# Symposion_K3_Arduino-Peripherie-IF_v2_2.net
KiCad netlist of a schematic drawn in EAGLE
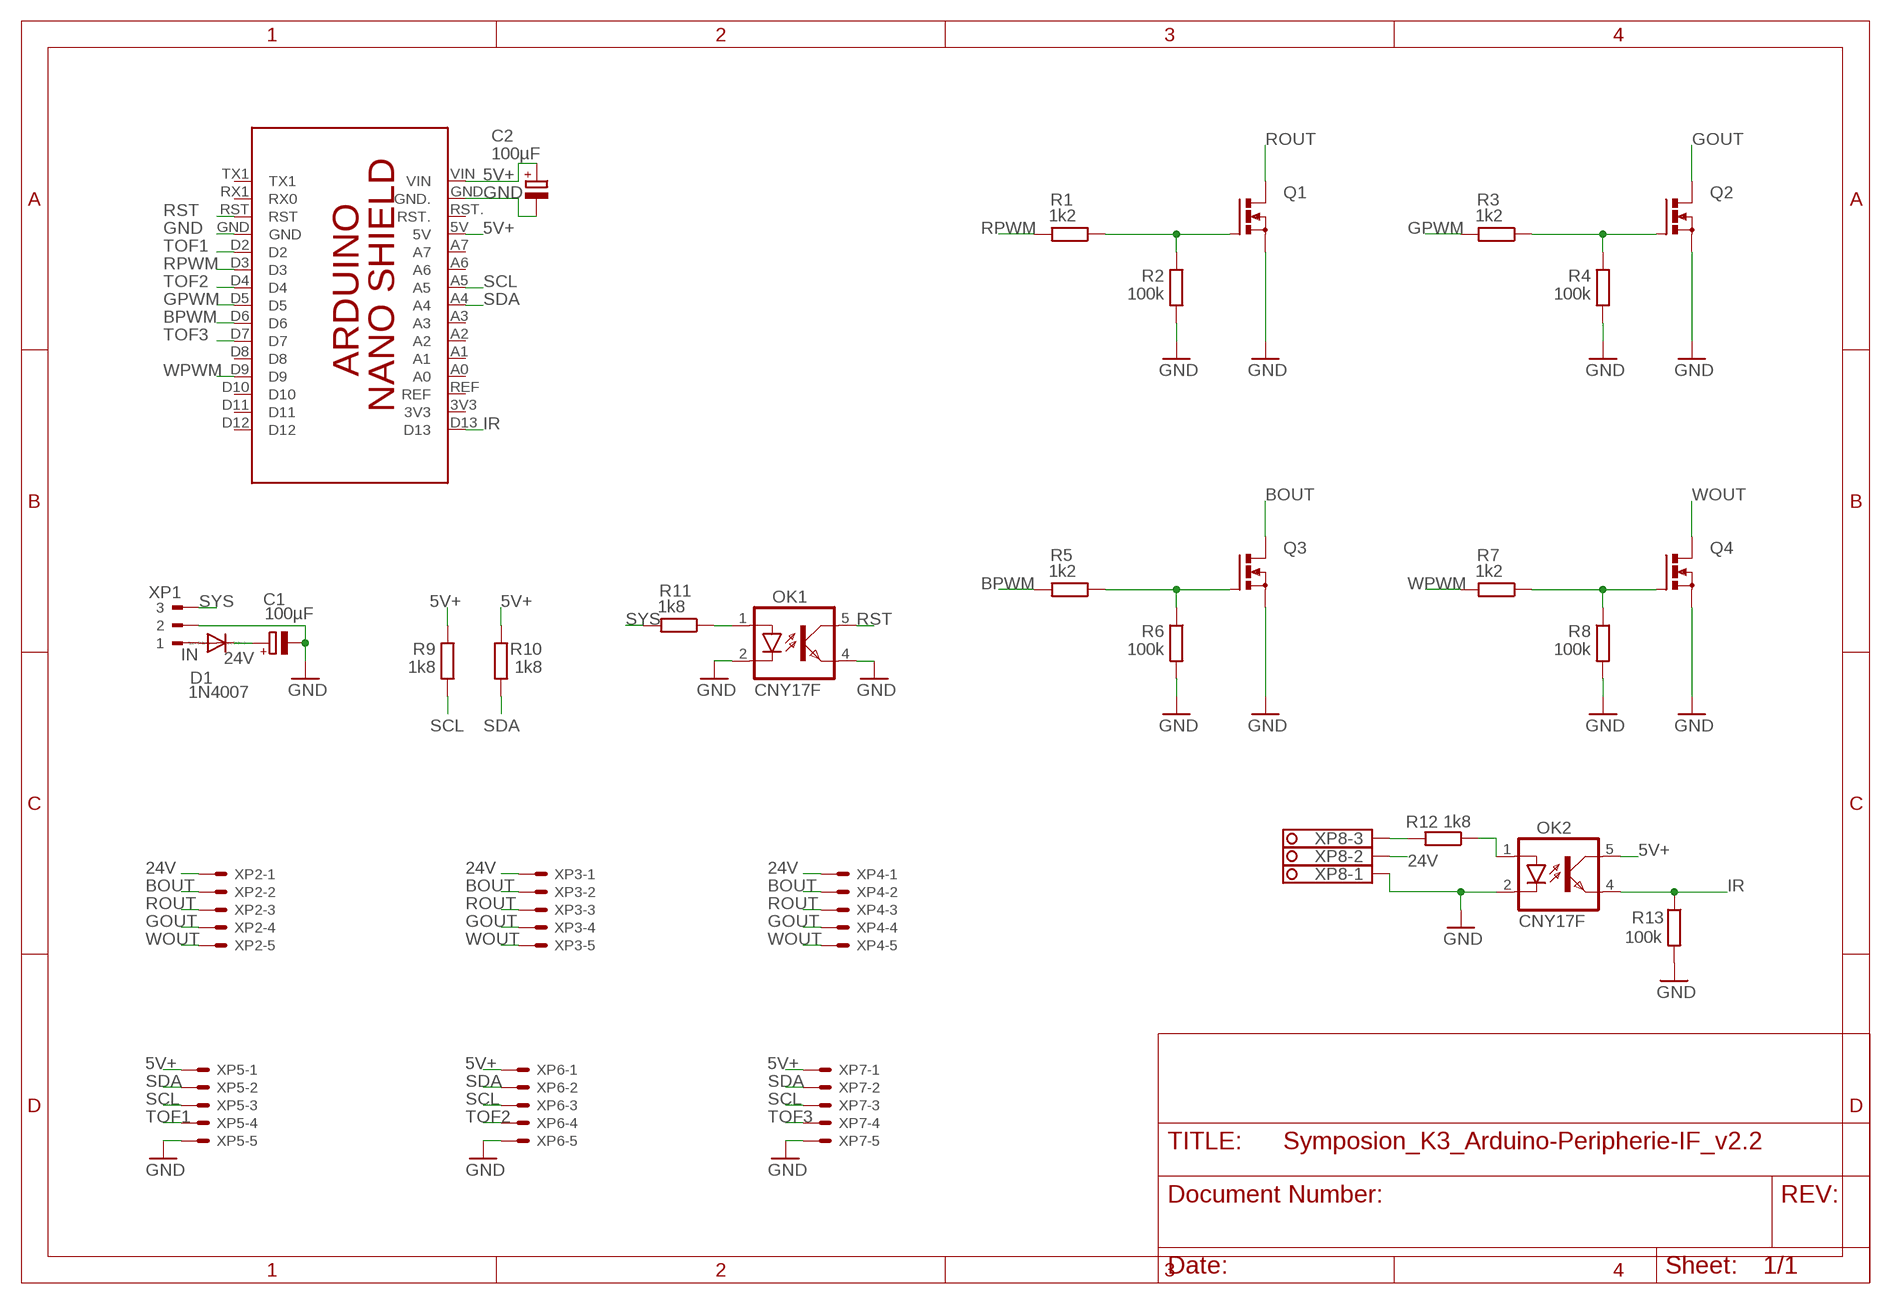
[diagram p0: schematic, sheet 1]

(export (version "E")
  (design (tool "Eeschema 10.0.6"))
  (components
    (comp (ref "C1")
      (value "100µF")
      (footprint "eagle-import:RCL_E5-6")
      (libsource (lib "eagle-import") (part "RCL_CPOL-EUE5-6"))
    )
    (comp (ref "C2")
      (value "100µF")
      (footprint "eagle-import:RCL_E5-6")
      (libsource (lib "eagle-import") (part "RCL_CPOL-EUE5-6"))
    )
    (comp (ref "D1")
      (value "1N4007")
      (footprint "eagle-import:DIODE_F126-10")
      (libsource (lib "eagle-import") (part "DIODE_DIODE-F126-10"))
    )
    (comp (ref "OK1")
      (value "CNY17F")
      (footprint "eagle-import:DIL06")
      (fields (field (name "MF") "VISHAY/TELEFUNKEN") (field (name "MPN") "CNY17F-3"))
      (libsource (lib "eagle-import") (part "CNY17F"))
    )
    (comp (ref "OK2")
      (value "CNY17F")
      (footprint "eagle-import:DIL06")
      (fields (field (name "MF") "VISHAY/TELEFUNKEN") (field (name "MPN") "CNY17F-3"))
      (libsource (lib "eagle-import") (part "CNY17F"))
    )
    (comp (ref "PCB1")
      (value "0_WSH_FAVORITES_ARDUINO_NANO")
      (footprint "eagle-import:0_WSH_FAVORITES_ARDUINO_NANO")
      (libsource (lib "eagle-import") (part "0_WSH_FAVORITES_ARDUINO_NANO"))
    )
    (comp (ref "Q1")
      (value "0_WSH_FAVORITES_BUZ11BV")
      (footprint "eagle-import:0_WSH_FAVORITES_TO220BV")
      (libsource (lib "eagle-import") (part "0_WSH_FAVORITES_BUZ11BV"))
    )
    (comp (ref "Q2")
      (value "0_WSH_FAVORITES_BUZ11BV")
      (footprint "eagle-import:0_WSH_FAVORITES_TO220BV")
      (libsource (lib "eagle-import") (part "0_WSH_FAVORITES_BUZ11BV"))
    )
    (comp (ref "Q3")
      (value "0_WSH_FAVORITES_BUZ11BV")
      (footprint "eagle-import:0_WSH_FAVORITES_TO220BV")
      (libsource (lib "eagle-import") (part "0_WSH_FAVORITES_BUZ11BV"))
    )
    (comp (ref "Q4")
      (value "0_WSH_FAVORITES_BUZ11BV")
      (footprint "eagle-import:0_WSH_FAVORITES_TO220BV")
      (libsource (lib "eagle-import") (part "0_WSH_FAVORITES_BUZ11BV"))
    )
    (comp (ref "R1")
      (value "1k2")
      (footprint "eagle-import:R1206")
      (libsource (lib "eagle-import") (part "R-EU_R1206"))
    )
    (comp (ref "R2")
      (value "100k")
      (footprint "eagle-import:R1206")
      (libsource (lib "eagle-import") (part "R-EU_R1206"))
    )
    (comp (ref "R3")
      (value "1k2")
      (footprint "eagle-import:R1206")
      (libsource (lib "eagle-import") (part "R-EU_R1206"))
    )
    (comp (ref "R4")
      (value "100k")
      (footprint "eagle-import:R1206")
      (libsource (lib "eagle-import") (part "R-EU_R1206"))
    )
    (comp (ref "R5")
      (value "1k2")
      (footprint "eagle-import:R1206")
      (libsource (lib "eagle-import") (part "R-EU_R1206"))
    )
    (comp (ref "R6")
      (value "100k")
      (footprint "eagle-import:R1206")
      (libsource (lib "eagle-import") (part "R-EU_R1206"))
    )
    (comp (ref "R7")
      (value "1k2")
      (footprint "eagle-import:R1206")
      (libsource (lib "eagle-import") (part "R-EU_R1206"))
    )
    (comp (ref "R8")
      (value "100k")
      (footprint "eagle-import:R1206")
      (libsource (lib "eagle-import") (part "R-EU_R1206"))
    )
    (comp (ref "R9")
      (value "1k8")
      (footprint "eagle-import:R1206")
      (libsource (lib "eagle-import") (part "R-EU_R1206"))
    )
    (comp (ref "R10")
      (value "1k8")
      (footprint "eagle-import:R1206")
      (libsource (lib "eagle-import") (part "R-EU_R1206"))
    )
    (comp (ref "R11")
      (value "1k8")
      (footprint "eagle-import:R1206")
      (libsource (lib "eagle-import") (part "R-EU_R1206"))
    )
    (comp (ref "R12")
      (value "1k8")
      (footprint "eagle-import:R1206")
      (libsource (lib "eagle-import") (part "R-EU_R1206"))
    )
    (comp (ref "R13")
      (value "100k")
      (footprint "eagle-import:R1206")
      (libsource (lib "eagle-import") (part "R-EU_R1206"))
    )
    (comp (ref "XP1")
      (value "180-3")
      (footprint "eagle-import:180-3")
      (libsource (lib "eagle-import") (part "180-3"))
    )
    (comp (ref "XP2")
      (value "22-27-2051-05")
      (footprint "eagle-import:6410-05")
      (fields (field (name "MF") "MOLEX"))
      (libsource (lib "eagle-import") (part "22-?-0527-2051"))
    )
    (comp (ref "XP3")
      (value "22-27-2051-05")
      (footprint "eagle-import:6410-05")
      (fields (field (name "MF") "MOLEX"))
      (libsource (lib "eagle-import") (part "22-?-0527-2051"))
    )
    (comp (ref "XP4")
      (value "22-27-2051-05")
      (footprint "eagle-import:6410-05")
      (fields (field (name "MF") "MOLEX"))
      (libsource (lib "eagle-import") (part "22-?-0527-2051"))
    )
    (comp (ref "XP5")
      (value "22-27-2051-05")
      (footprint "eagle-import:6410-05")
      (fields (field (name "MF") "MOLEX"))
      (libsource (lib "eagle-import") (part "22-?-0527-2051"))
    )
    (comp (ref "XP6")
      (value "22-27-2051-05")
      (footprint "eagle-import:6410-05")
      (fields (field (name "MF") "MOLEX"))
      (libsource (lib "eagle-import") (part "22-?-0527-2051"))
    )
    (comp (ref "XP7")
      (value "22-27-2051-05")
      (footprint "eagle-import:6410-05")
      (fields (field (name "MF") "MOLEX"))
      (libsource (lib "eagle-import") (part "22-?-0527-2051"))
    )
    (comp (ref "XP8")
      (value "1751251")
      (footprint "eagle-import:1751251")
      (libsource (lib "eagle-import") (part "1751251"))
    )
  )
  (nets
    (net (code "1") (name "/5V+") (class "Default")
      (node (ref "C2") (pin "+") (pinfunction "+_+") (pintype "passive"))
      (node (ref "OK2") (pin "5") (pinfunction "COL_5") (pintype "passive"))
      (node (ref "PCB1") (pin "5V") (pinfunction "5V_5V") (pintype "bidirectional"))
      (node (ref "PCB1") (pin "VIN") (pinfunction "VIN_VIN") (pintype "bidirectional"))
      (node (ref "R10") (pin "1") (pinfunction "1_1") (pintype "passive"))
      (node (ref "R9") (pin "1") (pinfunction "1_1") (pintype "passive"))
      (node (ref "XP5") (pin "1") (pinfunction "S_1") (pintype "passive"))
      (node (ref "XP6") (pin "1") (pinfunction "S_1") (pintype "passive"))
      (node (ref "XP7") (pin "1") (pinfunction "S_1") (pintype "passive"))
    )
    (net (code "2") (name "/24V") (class "Default")
      (node (ref "C1") (pin "+") (pinfunction "+_+") (pintype "passive"))
      (node (ref "D1") (pin "C") (pinfunction "C_C") (pintype "passive"))
      (node (ref "XP2") (pin "1") (pinfunction "S_1") (pintype "passive"))
      (node (ref "XP3") (pin "1") (pinfunction "S_1") (pintype "passive"))
      (node (ref "XP4") (pin "1") (pinfunction "S_1") (pintype "passive"))
      (node (ref "XP8") (pin "2") (pinfunction "K_2") (pintype "passive"))
    )
    (net (code "3") (name "/BOUT") (class "Default")
      (node (ref "Q3") (pin "D") (pinfunction "D_D") (pintype "passive"))
      (node (ref "XP2") (pin "2") (pinfunction "S_2") (pintype "passive"))
      (node (ref "XP3") (pin "2") (pinfunction "S_2") (pintype "passive"))
      (node (ref "XP4") (pin "2") (pinfunction "S_2") (pintype "passive"))
    )
    (net (code "4") (name "/BPWM") (class "Default")
      (node (ref "PCB1") (pin "D6") (pinfunction "D6_D6") (pintype "bidirectional"))
      (node (ref "R5") (pin "2") (pinfunction "2_2") (pintype "passive"))
    )
    (net (code "5") (name "/GOUT") (class "Default")
      (node (ref "Q2") (pin "D") (pinfunction "D_D") (pintype "passive"))
      (node (ref "XP2") (pin "4") (pinfunction "S_4") (pintype "passive"))
      (node (ref "XP3") (pin "4") (pinfunction "S_4") (pintype "passive"))
      (node (ref "XP4") (pin "4") (pinfunction "S_4") (pintype "passive"))
    )
    (net (code "6") (name "/GPWM") (class "Default")
      (node (ref "PCB1") (pin "D5") (pinfunction "D5_D5") (pintype "bidirectional"))
      (node (ref "R3") (pin "2") (pinfunction "2_2") (pintype "passive"))
    )
    (net (code "8") (name "/IR") (class "Default")
      (node (ref "OK2") (pin "4") (pinfunction "EMIT_4") (pintype "passive"))
      (node (ref "PCB1") (pin "D13") (pinfunction "D13_D13") (pintype "bidirectional"))
      (node (ref "R13") (pin "1") (pinfunction "1_1") (pintype "passive"))
    )
    (net (code "9") (name "/ROUT") (class "Default")
      (node (ref "Q1") (pin "D") (pinfunction "D_D") (pintype "passive"))
      (node (ref "XP2") (pin "3") (pinfunction "S_3") (pintype "passive"))
      (node (ref "XP3") (pin "3") (pinfunction "S_3") (pintype "passive"))
      (node (ref "XP4") (pin "3") (pinfunction "S_3") (pintype "passive"))
    )
    (net (code "10") (name "/RPWM") (class "Default")
      (node (ref "PCB1") (pin "D3") (pinfunction "D3_D3") (pintype "bidirectional"))
      (node (ref "R1") (pin "2") (pinfunction "2_2") (pintype "passive"))
    )
    (net (code "11") (name "/RST") (class "Default")
      (node (ref "OK1") (pin "5") (pinfunction "COL_5") (pintype "passive"))
      (node (ref "PCB1") (pin "RST") (pinfunction "RST_RST") (pintype "bidirectional"))
    )
    (net (code "12") (name "/SCL") (class "Default")
      (node (ref "PCB1") (pin "A5") (pinfunction "A5_A5") (pintype "bidirectional"))
      (node (ref "R9") (pin "2") (pinfunction "2_2") (pintype "passive"))
      (node (ref "XP5") (pin "3") (pinfunction "S_3") (pintype "passive"))
      (node (ref "XP6") (pin "3") (pinfunction "S_3") (pintype "passive"))
      (node (ref "XP7") (pin "3") (pinfunction "S_3") (pintype "passive"))
    )
    (net (code "13") (name "/SDA") (class "Default")
      (node (ref "PCB1") (pin "A4") (pinfunction "A4_A4") (pintype "bidirectional"))
      (node (ref "R10") (pin "2") (pinfunction "2_2") (pintype "passive"))
      (node (ref "XP5") (pin "2") (pinfunction "S_2") (pintype "passive"))
      (node (ref "XP6") (pin "2") (pinfunction "S_2") (pintype "passive"))
      (node (ref "XP7") (pin "2") (pinfunction "S_2") (pintype "passive"))
    )
    (net (code "14") (name "/SYS") (class "Default")
      (node (ref "R11") (pin "2") (pinfunction "2_2") (pintype "passive"))
      (node (ref "XP1") (pin "3") (pinfunction "3_3") (pintype "passive"))
    )
    (net (code "15") (name "/TOF1") (class "Default")
      (node (ref "PCB1") (pin "D2") (pinfunction "D2_D2") (pintype "bidirectional"))
      (node (ref "XP5") (pin "4") (pinfunction "S_4") (pintype "passive"))
    )
    (net (code "16") (name "/TOF2") (class "Default")
      (node (ref "PCB1") (pin "D4") (pinfunction "D4_D4") (pintype "bidirectional"))
      (node (ref "XP6") (pin "4") (pinfunction "S_4") (pintype "passive"))
    )
    (net (code "17") (name "/TOF3") (class "Default")
      (node (ref "PCB1") (pin "D7") (pinfunction "D7_D7") (pintype "bidirectional"))
      (node (ref "XP7") (pin "4") (pinfunction "S_4") (pintype "passive"))
    )
    (net (code "18") (name "/WOUT") (class "Default")
      (node (ref "Q4") (pin "D") (pinfunction "D_D") (pintype "passive"))
      (node (ref "XP2") (pin "5") (pinfunction "S_5") (pintype "passive"))
      (node (ref "XP3") (pin "5") (pinfunction "S_5") (pintype "passive"))
      (node (ref "XP4") (pin "5") (pinfunction "S_5") (pintype "passive"))
    )
    (net (code "19") (name "/WPWM") (class "Default")
      (node (ref "PCB1") (pin "D9") (pinfunction "D9_D9") (pintype "bidirectional"))
      (node (ref "R7") (pin "2") (pinfunction "2_2") (pintype "passive"))
    )
    (net (code "20") (name "GND") (class "Default")
      (node (ref "C1") (pin "-") (pinfunction "-_-") (pintype "passive"))
      (node (ref "C2") (pin "-") (pinfunction "-_-") (pintype "passive"))
      (node (ref "OK1") (pin "2") (pinfunction "C_2") (pintype "passive"))
      (node (ref "OK1") (pin "4") (pinfunction "EMIT_4") (pintype "passive"))
      (node (ref "OK2") (pin "2") (pinfunction "C_2") (pintype "passive"))
      (node (ref "PCB1") (pin "GND") (pinfunction "GND_GND") (pintype "bidirectional"))
      (node (ref "PCB1") (pin "GND.") (pinfunction "GND._GND.") (pintype "bidirectional"))
      (node (ref "Q1") (pin "S") (pinfunction "S_S") (pintype "passive"))
      (node (ref "Q2") (pin "S") (pinfunction "S_S") (pintype "passive"))
      (node (ref "Q3") (pin "S") (pinfunction "S_S") (pintype "passive"))
      (node (ref "Q4") (pin "S") (pinfunction "S_S") (pintype "passive"))
      (node (ref "R13") (pin "2") (pinfunction "2_2") (pintype "passive"))
      (node (ref "R2") (pin "2") (pinfunction "2_2") (pintype "passive"))
      (node (ref "R4") (pin "2") (pinfunction "2_2") (pintype "passive"))
      (node (ref "R6") (pin "2") (pinfunction "2_2") (pintype "passive"))
      (node (ref "R8") (pin "2") (pinfunction "2_2") (pintype "passive"))
      (node (ref "XP1") (pin "2") (pinfunction "2_2") (pintype "passive"))
      (node (ref "XP5") (pin "5") (pinfunction "S_5") (pintype "passive"))
      (node (ref "XP6") (pin "5") (pinfunction "S_5") (pintype "passive"))
      (node (ref "XP7") (pin "5") (pinfunction "S_5") (pintype "passive"))
      (node (ref "XP8") (pin "1") (pinfunction "K_1") (pintype "passive"))
    )
    (net (code "21") (name "Net-(D1-PadA)") (class "Default")
      (node (ref "D1") (pin "A") (pinfunction "A_A") (pintype "passive"))
      (node (ref "XP1") (pin "1") (pinfunction "1_1") (pintype "passive"))
    )
    (net (code "22") (name "Net-(OK1-A)") (class "Default")
      (node (ref "OK1") (pin "1") (pinfunction "A_1") (pintype "passive"))
      (node (ref "R11") (pin "1") (pinfunction "1_1") (pintype "passive"))
    )
    (net (code "23") (name "Net-(OK2-A)") (class "Default")
      (node (ref "OK2") (pin "1") (pinfunction "A_1") (pintype "passive"))
      (node (ref "R12") (pin "1") (pinfunction "1_1") (pintype "passive"))
    )
    (net (code "24") (name "Net-(Q1-PadG)") (class "Default")
      (node (ref "Q1") (pin "G") (pinfunction "G_G") (pintype "passive"))
      (node (ref "R1") (pin "1") (pinfunction "1_1") (pintype "passive"))
      (node (ref "R2") (pin "1") (pinfunction "1_1") (pintype "passive"))
    )
    (net (code "25") (name "Net-(Q2-PadG)") (class "Default")
      (node (ref "Q2") (pin "G") (pinfunction "G_G") (pintype "passive"))
      (node (ref "R3") (pin "1") (pinfunction "1_1") (pintype "passive"))
      (node (ref "R4") (pin "1") (pinfunction "1_1") (pintype "passive"))
    )
    (net (code "26") (name "Net-(Q3-PadG)") (class "Default")
      (node (ref "Q3") (pin "G") (pinfunction "G_G") (pintype "passive"))
      (node (ref "R5") (pin "1") (pinfunction "1_1") (pintype "passive"))
      (node (ref "R6") (pin "1") (pinfunction "1_1") (pintype "passive"))
    )
    (net (code "27") (name "Net-(Q4-PadG)") (class "Default")
      (node (ref "Q4") (pin "G") (pinfunction "G_G") (pintype "passive"))
      (node (ref "R7") (pin "1") (pinfunction "1_1") (pintype "passive"))
      (node (ref "R8") (pin "1") (pinfunction "1_1") (pintype "passive"))
    )
    (net (code "28") (name "Net-(XP8C-K)") (class "Default")
      (node (ref "R12") (pin "2") (pinfunction "2_2") (pintype "passive"))
      (node (ref "XP8") (pin "3") (pinfunction "K_3") (pintype "passive"))
    )
    (net (code "29") (name "unconnected-(PCB1-Pad3V3)") (class "Default")
      (node (ref "PCB1") (pin "3V3") (pinfunction "3V3_3V3") (pintype "bidirectional"))
    )
    (net (code "30") (name "unconnected-(PCB1-PadA0)") (class "Default")
      (node (ref "PCB1") (pin "A0") (pinfunction "A0_A0") (pintype "bidirectional"))
    )
    (net (code "31") (name "unconnected-(PCB1-PadA1)") (class "Default")
      (node (ref "PCB1") (pin "A1") (pinfunction "A1_A1") (pintype "bidirectional"))
    )
    (net (code "32") (name "unconnected-(PCB1-PadA2)") (class "Default")
      (node (ref "PCB1") (pin "A2") (pinfunction "A2_A2") (pintype "bidirectional"))
    )
    (net (code "33") (name "unconnected-(PCB1-PadA3)") (class "Default")
      (node (ref "PCB1") (pin "A3") (pinfunction "A3_A3") (pintype "bidirectional"))
    )
    (net (code "34") (name "unconnected-(PCB1-PadA6)") (class "Default")
      (node (ref "PCB1") (pin "A6") (pinfunction "A6_A6") (pintype "bidirectional"))
    )
    (net (code "35") (name "unconnected-(PCB1-PadA7)") (class "Default")
      (node (ref "PCB1") (pin "A7") (pinfunction "A7_A7") (pintype "bidirectional"))
    )
    (net (code "36") (name "unconnected-(PCB1-PadD8)") (class "Default")
      (node (ref "PCB1") (pin "D8") (pinfunction "D8_D8") (pintype "bidirectional"))
    )
    (net (code "37") (name "unconnected-(PCB1-PadD10)") (class "Default")
      (node (ref "PCB1") (pin "D10") (pinfunction "D10_D10") (pintype "bidirectional"))
    )
    (net (code "38") (name "unconnected-(PCB1-PadD11)") (class "Default")
      (node (ref "PCB1") (pin "D11") (pinfunction "D11_D11") (pintype "bidirectional"))
    )
    (net (code "39") (name "unconnected-(PCB1-PadD12)") (class "Default")
      (node (ref "PCB1") (pin "D12") (pinfunction "D12_D12") (pintype "bidirectional"))
    )
    (net (code "40") (name "unconnected-(PCB1-PadREF)") (class "Default")
      (node (ref "PCB1") (pin "REF") (pinfunction "REF_REF") (pintype "bidirectional"))
    )
    (net (code "41") (name "unconnected-(PCB1-PadRST.)") (class "Default")
      (node (ref "PCB1") (pin "RST.") (pinfunction "RST._RST.") (pintype "bidirectional"))
    )
    (net (code "42") (name "unconnected-(PCB1-PadTX1)") (class "Default")
      (node (ref "PCB1") (pin "TX1") (pinfunction "TX1_TX1") (pintype "bidirectional"))
    )
    (net (code "43") (name "unconnected-(PCB1-RX0-PadRX1)") (class "Default")
      (node (ref "PCB1") (pin "RX1") (pinfunction "RX0_RX1") (pintype "bidirectional"))
    )
  )
)
